# MCU.net
KiCad netlist of a schematic drawn in Altium Designer
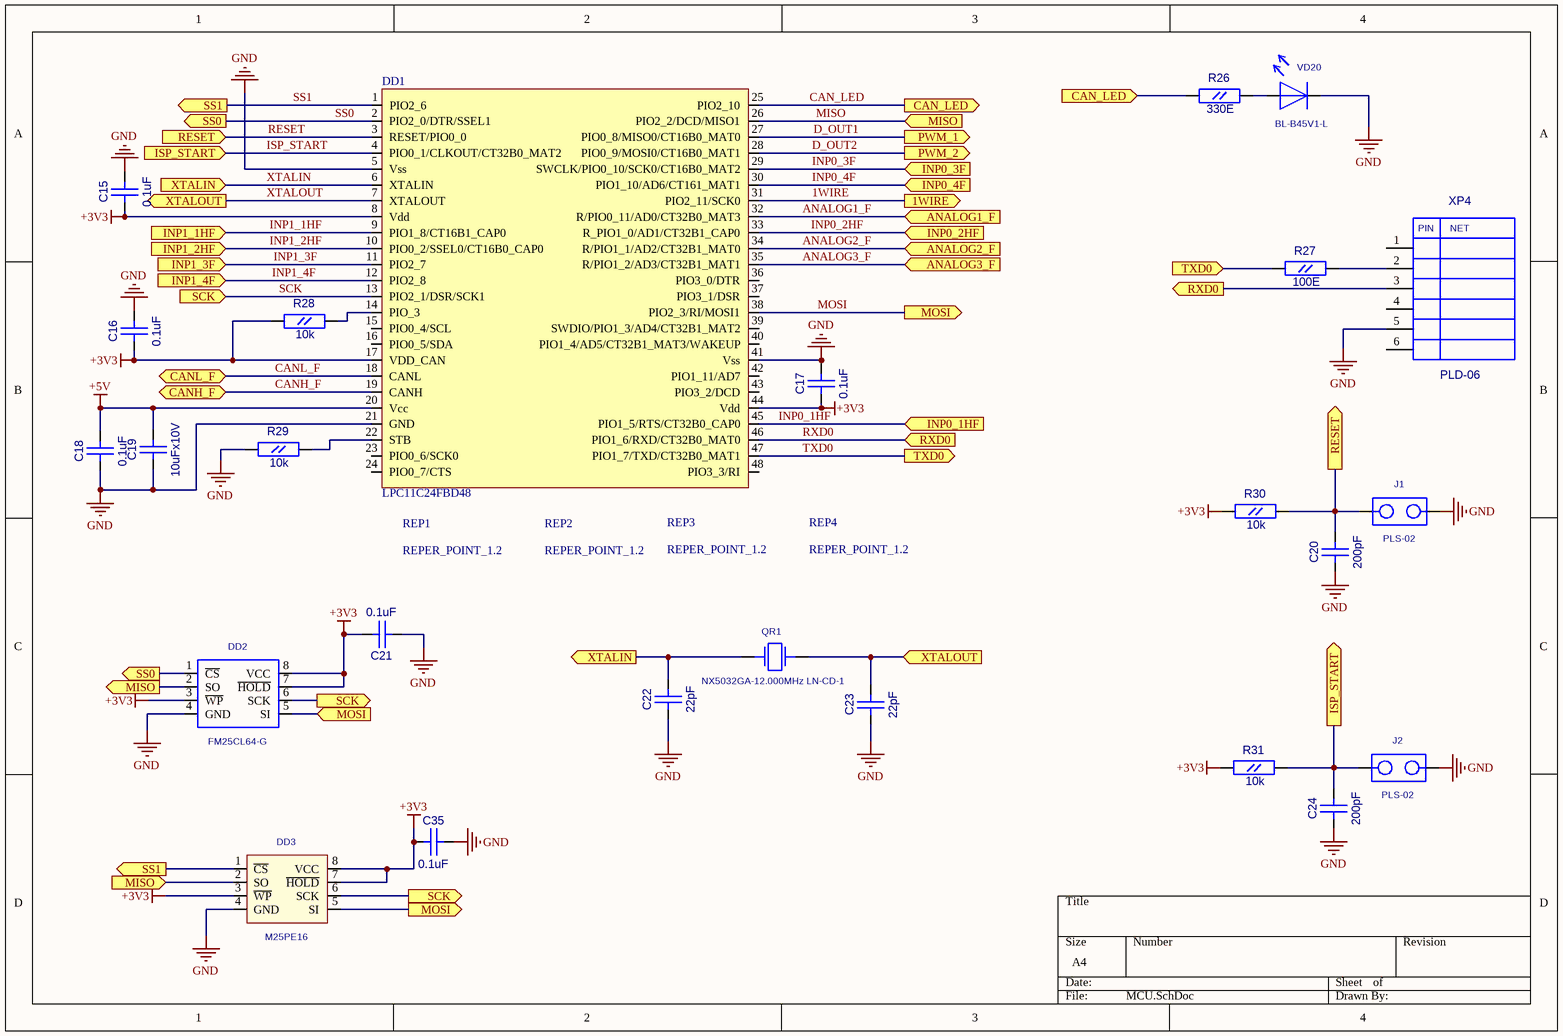
[diagram p0: MCU.SchDoc]

(export (version "E")
  (design (tool "Eeschema 10.0.6"))
  (components
    (comp (ref "C15")
      (value "0.1uF")
      (footprint "CC0603")
      (description "CC0603")
      (libsource (lib "gprs_modem_2") (part "CC0603"))
    )
    (comp (ref "C16")
      (value "0.1uF")
      (footprint "CC0603")
      (description "CC0603")
      (libsource (lib "gprs_modem_2") (part "CC0603"))
    )
    (comp (ref "C17")
      (value "0.1uF")
      (footprint "CC0603")
      (description "CC0603")
      (libsource (lib "gprs_modem_2") (part "CC0603"))
    )
    (comp (ref "C18")
      (value "0.1uF")
      (footprint "CC0603")
      (description "CC0603")
      (libsource (lib "gprs_modem_2") (part "CC0603"))
    )
    (comp (ref "C19")
      (value "10uFx10V")
      (footprint "CC0805")
      (description "CC0805")
      (libsource (lib "gprs_modem_2") (part "CC0805"))
    )
    (comp (ref "C20")
      (value "200pF")
      (footprint "CC0603")
      (description "CC0603")
      (libsource (lib "gprs_modem_2") (part "CC0603"))
    )
    (comp (ref "C21")
      (value "0.1uF")
      (footprint "CC0603-3M")
      (description "CC0603")
      (libsource (lib "gprs_modem2") (part "CC0603"))
    )
    (comp (ref "C22")
      (value "22pF")
      (footprint "CC0603")
      (description "CC0603")
      (libsource (lib "gprs_modem_2") (part "CC0603"))
    )
    (comp (ref "C23")
      (value "22pF")
      (footprint "CC0603")
      (description "CC0603")
      (libsource (lib "gprs_modem_2") (part "CC0603"))
    )
    (comp (ref "C24")
      (value "200pF")
      (footprint "CC0603")
      (description "CC0603")
      (libsource (lib "gprs_modem_2") (part "CC0603"))
    )
    (comp (ref "C35")
      (value "0.1uF")
      (footprint "CC0603")
      (description "CC0603")
      (libsource (lib "gprs_modem_2") (part "CC0603"))
    )
    (comp (ref "DD1")
      (value "LPC11C24FBD48")
      (footprint "LQFP-48")
      (libsource (lib "gprs_modem_2") (part "LPC11C24FBD48"))
    )
    (comp (ref "DD2")
      (value "FM25CL64-G")
      (footprint "SO-8")
      (libsource (lib "gprs_modem_2") (part "FM25CL64-G"))
    )
    (comp (ref "DD3")
      (value "M25PE16")
      (footprint "EIAJ_SO8")
      (description "S25FL016A0LMFI01")
      (libsource (lib "gprs_modem_2") (part "S25FL016A0LMFI01"))
    )
    (comp (ref "J1") (value "PLS-02") (footprint "PLS-02") (libsource (lib "gprs_modem_2") (part "PLS-02")))
    (comp (ref "J2") (value "PLS-02") (footprint "PLS-02") (libsource (lib "gprs_modem_2") (part "PLS-02")))
    (comp (ref "QR1")
      (value "NX5032GA-12.000MHz LN-CD-1")
      (footprint "AC5032_2")
      (description "AC5032/2")
      (libsource (lib "gprs_modem_2") (part "AC5032_2"))
    )
    (comp (ref "R26")
      (value "330E")
      (footprint "RC0603")
      (description "RC0603")
      (libsource (lib "gprs_modem_2") (part "RC0603"))
    )
    (comp (ref "R27")
      (value "100E")
      (footprint "RC0603")
      (description "RC0603")
      (libsource (lib "gprs_modem_2") (part "RC0603"))
    )
    (comp (ref "R28")
      (value "10k")
      (footprint "RC0603")
      (description "RC0603")
      (libsource (lib "gprs_modem_2") (part "RC0603"))
    )
    (comp (ref "R29")
      (value "10k")
      (footprint "RC0603")
      (description "RC0603")
      (libsource (lib "gprs_modem_2") (part "RC0603"))
    )
    (comp (ref "R30")
      (value "10k")
      (footprint "RC0603")
      (description "RC0603")
      (libsource (lib "gprs_modem_2") (part "RC0603"))
    )
    (comp (ref "R31")
      (value "10k")
      (footprint "RC0603")
      (description "RC0603")
      (libsource (lib "gprs_modem_2") (part "RC0603"))
    )
    (comp (ref "REP1")
      (value "REPER_POINT_1.2")
      (footprint "REPER1.2")
      (description "REPER1.2")
      (libsource (lib "gprs_modem_2") (part "REPER1.2"))
    )
    (comp (ref "REP2")
      (value "REPER_POINT_1.2")
      (footprint "REPER1.2")
      (description "REPER1.2")
      (libsource (lib "gprs_modem_2") (part "REPER1.2"))
    )
    (comp (ref "REP3")
      (value "REPER_POINT_1.2")
      (footprint "REPER1.2")
      (description "REPER1.2")
      (libsource (lib "gprs_modem_2") (part "REPER1.2"))
    )
    (comp (ref "REP4")
      (value "REPER_POINT_1.2")
      (footprint "REPER1.2")
      (description "REPER1.2")
      (libsource (lib "gprs_modem_2") (part "REPER1.2"))
    )
    (comp (ref "VD20")
      (value "BL-B45V1-L")
      (footprint "LED3")
      (description "LED_3")
      (libsource (lib "gprs_modem_2") (part "LED_3"))
    )
    (comp (ref "XP4")
      (value "PLD-06")
      (footprint "PIN6")
      (description "PLD06")
      (libsource (lib "gprs_modem_2") (part "PLD-06"))
    )
  )
  (nets
    (net (code "1") (name "+3V3") (class "Default")
      (node (ref "C15") (pin "1") (pinfunction "A_1") (pintype "passive"))
      (node (ref "C16") (pin "1") (pinfunction "A_1") (pintype "passive"))
      (node (ref "C17") (pin "1") (pinfunction "A_1") (pintype "passive"))
      (node (ref "C21") (pin "2") (pinfunction "B_2") (pintype "passive"))
      (node (ref "C35") (pin "1") (pinfunction "A_1") (pintype "passive"))
      (node (ref "DD1") (pin "17") (pinfunction "VDD_CAN_17") (pintype "passive"))
      (node (ref "DD1") (pin "44") (pinfunction "Vdd_44") (pintype "passive"))
      (node (ref "DD1") (pin "8") (pinfunction "Vdd_8") (pintype "passive"))
      (node (ref "DD2") (pin "3") (pinfunction "~{WP}_3") (pintype "passive"))
      (node (ref "DD2") (pin "7") (pinfunction "~{HOLD}_7") (pintype "passive"))
      (node (ref "DD2") (pin "8") (pinfunction "VCC_8") (pintype "passive"))
      (node (ref "DD3") (pin "3") (pinfunction "~{WP}_3") (pintype "passive"))
      (node (ref "DD3") (pin "7") (pinfunction "~{HOLD}_7") (pintype "passive"))
      (node (ref "DD3") (pin "8") (pinfunction "VCC_8") (pintype "passive"))
      (node (ref "R28") (pin "1") (pinfunction "A_1") (pintype "passive"))
      (node (ref "R30") (pin "1") (pinfunction "A_1") (pintype "passive"))
      (node (ref "R31") (pin "1") (pinfunction "A_1") (pintype "passive"))
    )
    (net (code "2") (name "+5V") (class "Default")
      (node (ref "C18") (pin "2") (pinfunction "B_2") (pintype "passive"))
      (node (ref "C19") (pin "2") (pinfunction "B_2") (pintype "passive"))
      (node (ref "DD1") (pin "20") (pinfunction "Vcc_20") (pintype "passive"))
    )
    (net (code "3") (name "/1WIRE") (class "Default")
      (node (ref "DD1") (pin "31") (pinfunction "PIO2_11/SCK0_31") (pintype "passive"))
    )
    (net (code "4") (name "/ANALOG1_F") (class "Default")
      (node (ref "DD1") (pin "32") (pinfunction "R/PIO0_11/AD0/CT32B0_MAT3_32") (pintype "passive"))
    )
    (net (code "5") (name "/ANALOG2_F") (class "Default")
      (node (ref "DD1") (pin "34") (pinfunction "R/PIO1_1/AD2/CT32B1_MAT0_34") (pintype "passive"))
    )
    (net (code "6") (name "/ANALOG3_F") (class "Default")
      (node (ref "DD1") (pin "35") (pinfunction "R/PIO1_2/AD3/CT32B1_MAT1_35") (pintype "passive"))
    )
    (net (code "7") (name "/CANH_F") (class "Default")
      (node (ref "DD1") (pin "19") (pinfunction "CANH_19") (pintype "passive"))
    )
    (net (code "8") (name "/CANL_F") (class "Default")
      (node (ref "DD1") (pin "18") (pinfunction "CANL_18") (pintype "passive"))
    )
    (net (code "9") (name "/CAN_LED") (class "Default")
      (node (ref "DD1") (pin "25") (pinfunction "PIO2_10_25") (pintype "passive"))
      (node (ref "R26") (pin "1") (pinfunction "A_1") (pintype "passive"))
    )
    (net (code "10") (name "/D_OUT1") (class "Default")
      (node (ref "DD1") (pin "27") (pinfunction "PIO0_8/MISO0/CT16B0_MAT0_27") (pintype "passive"))
    )
    (net (code "11") (name "/D_OUT2") (class "Default")
      (node (ref "DD1") (pin "28") (pinfunction "PIO0_9/MOSI0/CT16B0_MAT1_28") (pintype "passive"))
    )
    (net (code "12") (name "/INP0_1HF") (class "Default")
      (node (ref "DD1") (pin "45") (pinfunction "PIO1_5/RTS/CT32B0_CAP0_45") (pintype "passive"))
    )
    (net (code "13") (name "/INP0_2HF") (class "Default")
      (node (ref "DD1") (pin "33") (pinfunction "R_PIO1_0/AD1/CT32B1_CAP0_33") (pintype "passive"))
    )
    (net (code "14") (name "/INP0_3F") (class "Default")
      (node (ref "DD1") (pin "29") (pinfunction "SWCLK/PIO0_10/SCK0/CT16B0_MAT2_29") (pintype "passive"))
    )
    (net (code "15") (name "/INP0_4F") (class "Default")
      (node (ref "DD1") (pin "30") (pinfunction "PIO1_10/AD6/CT161_MAT1_30") (pintype "passive"))
    )
    (net (code "16") (name "/INP1_1HF") (class "Default")
      (node (ref "DD1") (pin "9") (pinfunction "PIO1_8/CT16B1_CAP0_9") (pintype "passive"))
    )
    (net (code "17") (name "/INP1_2HF") (class "Default")
      (node (ref "DD1") (pin "10") (pinfunction "PIO0_2/SSEL0/CT16B0_CAP0_10") (pintype "passive"))
    )
    (net (code "18") (name "/INP1_3F") (class "Default")
      (node (ref "DD1") (pin "11") (pinfunction "PIO2_7_11") (pintype "passive"))
    )
    (net (code "19") (name "/INP1_4F") (class "Default")
      (node (ref "DD1") (pin "12") (pinfunction "PIO2_8_12") (pintype "passive"))
    )
    (net (code "20") (name "/ISP_START") (class "Default")
      (node (ref "C24") (pin "2") (pinfunction "B_2") (pintype "passive"))
      (node (ref "DD1") (pin "4") (pinfunction "PIO0_1/CLKOUT/CT32B0_MAT2_4") (pintype "passive"))
      (node (ref "J2") (pin "1") (pintype "passive"))
      (node (ref "R31") (pin "2") (pinfunction "B_2") (pintype "passive"))
    )
    (net (code "21") (name "/MISO") (class "Default")
      (node (ref "DD1") (pin "26") (pinfunction "PIO2_2/DCD/MISO1_26") (pintype "passive"))
      (node (ref "DD2") (pin "2") (pinfunction "SO_2") (pintype "passive"))
      (node (ref "DD3") (pin "2") (pinfunction "SO_2") (pintype "passive"))
    )
    (net (code "22") (name "/MOSI") (class "Default")
      (node (ref "DD1") (pin "38") (pinfunction "PIO2_3/RI/MOSI1_38") (pintype "passive"))
      (node (ref "DD2") (pin "5") (pinfunction "SI_5") (pintype "passive"))
      (node (ref "DD3") (pin "5") (pinfunction "SI_5") (pintype "passive"))
    )
    (net (code "23") (name "/RESET") (class "Default")
      (node (ref "C20") (pin "2") (pinfunction "B_2") (pintype "passive"))
      (node (ref "DD1") (pin "3") (pinfunction "RESET/PIO0_0_3") (pintype "passive"))
      (node (ref "J1") (pin "1") (pintype "passive"))
      (node (ref "R30") (pin "2") (pinfunction "B_2") (pintype "passive"))
    )
    (net (code "24") (name "/RXD0") (class "Default")
      (node (ref "DD1") (pin "46") (pinfunction "PIO1_6/RXD/CT32B0_MAT0_46") (pintype "passive"))
      (node (ref "XP4") (pin "3") (pinfunction "3_3") (pintype "passive"))
    )
    (net (code "25") (name "/SCK") (class "Default")
      (node (ref "DD1") (pin "13") (pinfunction "PIO2_1/DSR/SCK1_13") (pintype "passive"))
      (node (ref "DD2") (pin "6") (pinfunction "SCK_6") (pintype "passive"))
      (node (ref "DD3") (pin "6") (pinfunction "SCK_6") (pintype "passive"))
    )
    (net (code "26") (name "/SS0") (class "Default")
      (node (ref "DD1") (pin "2") (pinfunction "PIO2_0/DTR/SSEL1_2") (pintype "passive"))
      (node (ref "DD2") (pin "1") (pinfunction "~{CS}_1") (pintype "passive"))
    )
    (net (code "27") (name "/SS1") (class "Default")
      (node (ref "DD1") (pin "1") (pinfunction "PIO2_6_1") (pintype "passive"))
      (node (ref "DD3") (pin "1") (pinfunction "~{CS}_1") (pintype "passive"))
    )
    (net (code "28") (name "/TXD0") (class "Default")
      (node (ref "DD1") (pin "47") (pinfunction "PIO1_7/TXD/CT32B0_MAT1_47") (pintype "passive"))
      (node (ref "R27") (pin "1") (pinfunction "A_1") (pintype "passive"))
    )
    (net (code "29") (name "/XTALIN") (class "Default")
      (node (ref "C22") (pin "2") (pinfunction "B_2") (pintype "passive"))
      (node (ref "DD1") (pin "6") (pinfunction "XTALIN_6") (pintype "passive"))
      (node (ref "QR1") (pin "1") (pintype "passive"))
    )
    (net (code "30") (name "/XTALOUT") (class "Default")
      (node (ref "C23") (pin "2") (pinfunction "B_2") (pintype "passive"))
      (node (ref "DD1") (pin "7") (pinfunction "XTALOUT_7") (pintype "passive"))
      (node (ref "QR1") (pin "2") (pintype "passive"))
    )
    (net (code "31") (name "GND") (class "Default")
      (node (ref "C15") (pin "2") (pinfunction "B_2") (pintype "passive"))
      (node (ref "C16") (pin "2") (pinfunction "B_2") (pintype "passive"))
      (node (ref "C17") (pin "2") (pinfunction "B_2") (pintype "passive"))
      (node (ref "C18") (pin "1") (pinfunction "A_1") (pintype "passive"))
      (node (ref "C19") (pin "1") (pinfunction "A_1") (pintype "passive"))
      (node (ref "C20") (pin "1") (pinfunction "A_1") (pintype "passive"))
      (node (ref "C21") (pin "1") (pinfunction "A_1") (pintype "passive"))
      (node (ref "C22") (pin "1") (pinfunction "A_1") (pintype "passive"))
      (node (ref "C23") (pin "1") (pinfunction "A_1") (pintype "passive"))
      (node (ref "C24") (pin "1") (pinfunction "A_1") (pintype "passive"))
      (node (ref "C35") (pin "2") (pinfunction "B_2") (pintype "passive"))
      (node (ref "DD1") (pin "21") (pinfunction "GND_21") (pintype "passive"))
      (node (ref "DD1") (pin "41") (pinfunction "Vss_41") (pintype "passive"))
      (node (ref "DD1") (pin "5") (pinfunction "Vss_5") (pintype "passive"))
      (node (ref "DD2") (pin "4") (pinfunction "GND_4") (pintype "passive"))
      (node (ref "DD3") (pin "4") (pinfunction "GND_4") (pintype "passive"))
      (node (ref "J1") (pin "2") (pintype "passive"))
      (node (ref "J2") (pin "2") (pintype "passive"))
      (node (ref "R29") (pin "1") (pinfunction "A_1") (pintype "passive"))
      (node (ref "VD20") (pin "1") (pintype "passive"))
      (node (ref "XP4") (pin "5") (pinfunction "5_5") (pintype "passive"))
    )
    (net (code "32") (name "Net-(DD1-PIO_3)") (class "Default")
      (node (ref "DD1") (pin "14") (pinfunction "PIO_3_14") (pintype "passive"))
      (node (ref "R28") (pin "2") (pinfunction "B_2") (pintype "passive"))
    )
    (net (code "33") (name "Net-(DD1-STB)") (class "Default")
      (node (ref "DD1") (pin "22") (pinfunction "STB_22") (pintype "passive"))
      (node (ref "R29") (pin "2") (pinfunction "B_2") (pintype "passive"))
    )
    (net (code "34") (name "Net-(R26-B)") (class "Default")
      (node (ref "R26") (pin "2") (pinfunction "B_2") (pintype "passive"))
      (node (ref "VD20") (pin "2") (pintype "passive"))
    )
    (net (code "35") (name "Net-(R27-B)") (class "Default")
      (node (ref "R27") (pin "2") (pinfunction "B_2") (pintype "passive"))
      (node (ref "XP4") (pin "2") (pinfunction "2_2") (pintype "passive"))
    )
    (net (code "36") (name "unconnected-(DD1-PIO0_4{slash}SCL-Pad15)") (class "Default")
      (node (ref "DD1") (pin "15") (pinfunction "PIO0_4/SCL_15") (pintype "passive"))
    )
    (net (code "37") (name "unconnected-(DD1-PIO0_5{slash}SDA-Pad16)") (class "Default")
      (node (ref "DD1") (pin "16") (pinfunction "PIO0_5/SDA_16") (pintype "passive"))
    )
    (net (code "38") (name "unconnected-(DD1-PIO0_6{slash}SCK0-Pad23)") (class "Default")
      (node (ref "DD1") (pin "23") (pinfunction "PIO0_6/SCK0_23") (pintype "passive"))
    )
    (net (code "39") (name "unconnected-(DD1-PIO0_7{slash}CTS-Pad24)") (class "Default")
      (node (ref "DD1") (pin "24") (pinfunction "PIO0_7/CTS_24") (pintype "passive"))
    )
    (net (code "40") (name "unconnected-(DD1-PIO1_4{slash}AD5{slash}CT32B1_MAT3{slash}WAKEUP-Pad40)") (class "Default")
      (node (ref "DD1") (pin "40") (pinfunction "PIO1_4/AD5/CT32B1_MAT3/WAKEUP_40") (pintype "passive"))
    )
    (net (code "41") (name "unconnected-(DD1-PIO1_11{slash}AD7-Pad42)") (class "Default")
      (node (ref "DD1") (pin "42") (pinfunction "PIO1_11/AD7_42") (pintype "passive"))
    )
    (net (code "42") (name "unconnected-(DD1-PIO3_0{slash}DTR-Pad36)") (class "Default")
      (node (ref "DD1") (pin "36") (pinfunction "PIO3_0/DTR_36") (pintype "passive"))
    )
    (net (code "43") (name "unconnected-(DD1-PIO3_1{slash}DSR-Pad37)") (class "Default")
      (node (ref "DD1") (pin "37") (pinfunction "PIO3_1/DSR_37") (pintype "passive"))
    )
    (net (code "44") (name "unconnected-(DD1-PIO3_2{slash}DCD-Pad43)") (class "Default")
      (node (ref "DD1") (pin "43") (pinfunction "PIO3_2/DCD_43") (pintype "passive"))
    )
    (net (code "45") (name "unconnected-(DD1-PIO3_3{slash}RI-Pad48)") (class "Default")
      (node (ref "DD1") (pin "48") (pinfunction "PIO3_3/RI_48") (pintype "passive"))
    )
    (net (code "46") (name "unconnected-(DD1-SWDIO{slash}PIO1_3{slash}AD4{slash}CT32B1_MAT2-Pad39)") (class "Default")
      (node (ref "DD1") (pin "39") (pinfunction "SWDIO/PIO1_3/AD4/CT32B1_MAT2_39") (pintype "passive"))
    )
    (net (code "47") (name "unconnected-(REP1-Pad1)") (class "Default")
      (node (ref "REP1") (pin "1") (pintype "passive"))
    )
    (net (code "48") (name "unconnected-(REP2-Pad1)") (class "Default")
      (node (ref "REP2") (pin "1") (pintype "passive"))
    )
    (net (code "49") (name "unconnected-(REP3-Pad1)") (class "Default")
      (node (ref "REP3") (pin "1") (pintype "passive"))
    )
    (net (code "50") (name "unconnected-(REP4-Pad1)") (class "Default")
      (node (ref "REP4") (pin "1") (pintype "passive"))
    )
    (net (code "51") (name "unconnected-(XP4-Pad1)") (class "Default")
      (node (ref "XP4") (pin "1") (pinfunction "1_1") (pintype "passive"))
    )
    (net (code "52") (name "unconnected-(XP4-Pad4)") (class "Default")
      (node (ref "XP4") (pin "4") (pinfunction "4_4") (pintype "passive"))
    )
    (net (code "53") (name "unconnected-(XP4-Pad6)") (class "Default")
      (node (ref "XP4") (pin "6") (pinfunction "6_6") (pintype "passive"))
    )
  )
)
